# VT_12S_RHS_V0_1.net
KiCad netlist of a schematic drawn in Altium Designer
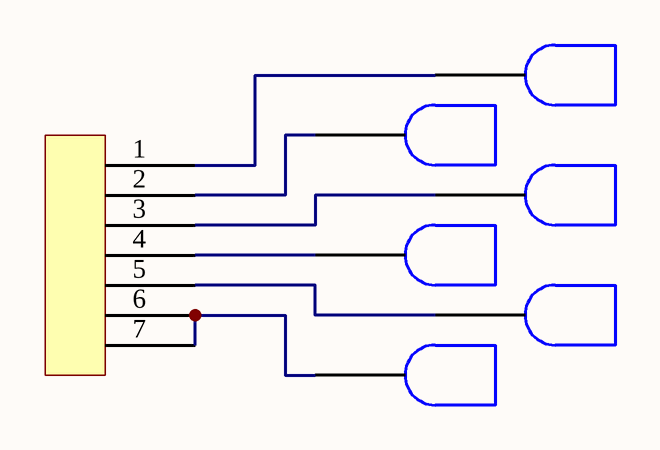
[diagram p0: VT 12S RHS V0.1.SchDoc]

(export (version "E")
  (design (tool "Eeschema 10.0.6"))
  (components
    (comp (ref "J1")
      (value "Voltage Tap")
      (footprint "Voltage Tap")
      (libsource (lib "Voltage Taps V0.1") (part "Voltage Tap"))
    )
    (comp (ref "J2")
      (value "Voltage Tap")
      (footprint "Voltage Tap")
      (libsource (lib "Voltage Taps V0.1") (part "Voltage Tap"))
    )
    (comp (ref "J3")
      (value "Voltage Tap")
      (footprint "Voltage Tap")
      (libsource (lib "Voltage Taps V0.1") (part "Voltage Tap"))
    )
    (comp (ref "J4")
      (value "Voltage Tap")
      (footprint "Voltage Tap")
      (libsource (lib "Voltage Taps V0.1") (part "Voltage Tap"))
    )
    (comp (ref "J5")
      (value "Voltage Tap")
      (footprint "Voltage Tap")
      (libsource (lib "Voltage Taps V0.1") (part "Voltage Tap"))
    )
    (comp (ref "J6")
      (value "84953-7-FPC")
      (footprint "84953-7 - FPC")
      (description "FPC Connectors, Flex-to-Board, 7 Position, .039 in [1 mm] Centerline, FPC Side Connector")
      (libsource (lib "TE_Con") (part "84953-7-FPC"))
    )
    (comp (ref "J7")
      (value "Voltage Tap")
      (footprint "Voltage Tap")
      (libsource (lib "Voltage Taps V0.1") (part "Voltage Tap"))
    )
  )
  (nets
    (net (code "1") (name "Net-(J1-Pad1)") (class "Default")
      (node (ref "J1") (pin "1") (pintype "passive"))
      (node (ref "J6") (pin "1") (pintype "passive"))
    )
    (net (code "2") (name "Net-(J2-Pad1)") (class "Default")
      (node (ref "J2") (pin "1") (pintype "passive"))
      (node (ref "J6") (pin "2") (pintype "passive"))
    )
    (net (code "3") (name "Net-(J3-Pad1)") (class "Default")
      (node (ref "J3") (pin "1") (pintype "passive"))
      (node (ref "J6") (pin "3") (pintype "passive"))
    )
    (net (code "4") (name "Net-(J4-Pad1)") (class "Default")
      (node (ref "J4") (pin "1") (pintype "passive"))
      (node (ref "J6") (pin "4") (pintype "passive"))
    )
    (net (code "5") (name "Net-(J5-Pad1)") (class "Default")
      (node (ref "J5") (pin "1") (pintype "passive"))
      (node (ref "J6") (pin "5") (pintype "passive"))
    )
    (net (code "6") (name "Net-(J6-Pad6)") (class "Default")
      (node (ref "J6") (pin "6") (pintype "passive"))
      (node (ref "J6") (pin "7") (pintype "passive"))
      (node (ref "J7") (pin "1") (pintype "passive"))
    )
  )
)
